# IO.net
KiCad netlist of a schematic drawn in Altium Designer
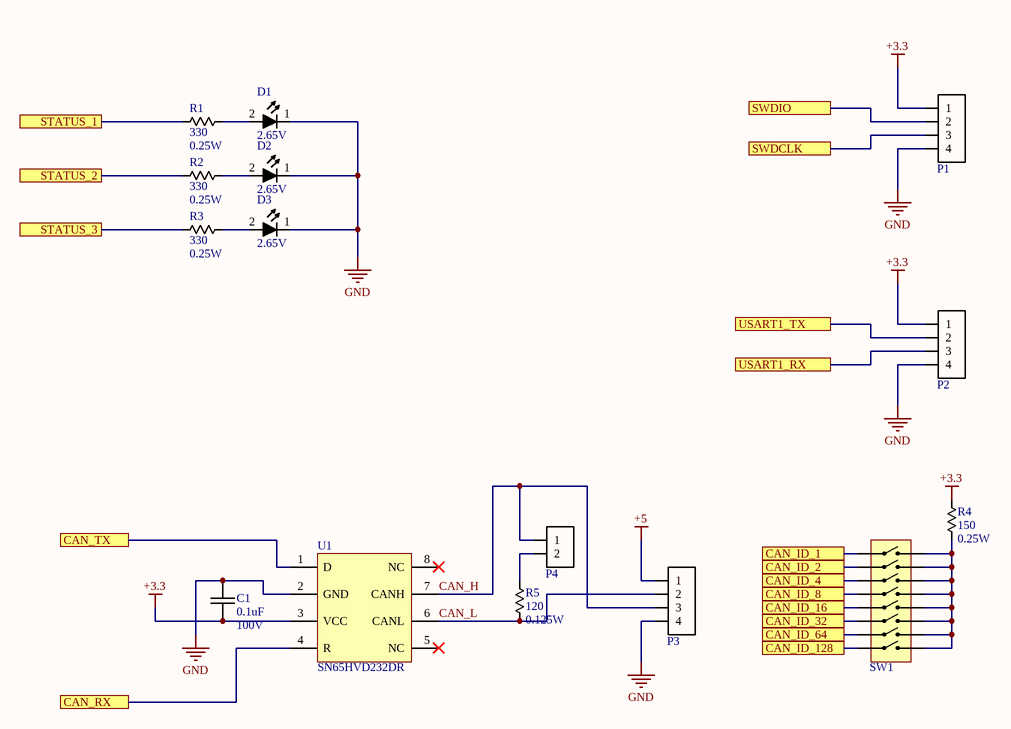
[diagram p0: IO.SchDoc]

(export (version "E")
  (design (tool "Eeschema 10.0.6"))
  (components
    (comp (ref "C1")
      (value "cap_single_np")
      (footprint "chip_0603")
      (description "CAP, 0.1uF, ±10%, 100V, X7R, 0603")
      (fields
        (field (name "TOLERANCE") "±10%")
        (field (name "CAPACITANCE") "0.1uF")
        (field (name "VOLTAGE RATING") "100V")
        (field (name "PART NUMBER") "CAP-00477")
      )
      (libsource (lib "Capacitors") (part "cap_single_np"))
    )
    (comp (ref "D1")
      (value "diode_4")
      (footprint "chip_0603")
      (description "LED, Blue, 0603, Low current, HELI2 Series")
      (fields
        (field (name "FORWARD VOLTAGE") "2.65V")
        (field (name "PART NUMBER") "DIO-00049")
        (field (name "MANUFACTURER") "Kingbright")
      )
      (libsource (lib "Diodes") (part "diode_4"))
    )
    (comp (ref "D2")
      (value "diode_4")
      (footprint "chip_0603")
      (description "LED, Blue, 0603, Low current, HELI2 Series")
      (fields
        (field (name "FORWARD VOLTAGE") "2.65V")
        (field (name "PART NUMBER") "DIO-00049")
        (field (name "MANUFACTURER") "Kingbright")
      )
      (libsource (lib "Diodes") (part "diode_4"))
    )
    (comp (ref "D3")
      (value "diode_4")
      (footprint "chip_0603")
      (description "LED, Blue, 0603, Low current, HELI2 Series")
      (fields
        (field (name "FORWARD VOLTAGE") "2.65V")
        (field (name "PART NUMBER") "DIO-00049")
        (field (name "MANUFACTURER") "Kingbright")
      )
      (libsource (lib "Diodes") (part "diode_4"))
    )
    (comp (ref "P1")
      (value "conn-4x1_0")
      (footprint "HDDR_4x1_0")
      (description "Header 4x1, 0.1\"")
      (fields (field (name "PART NUMBER") "CONN-00029"))
      (libsource (lib "Connectors") (part "conn-4x1_0"))
    )
    (comp (ref "P2")
      (value "conn-4x1_0")
      (footprint "HDDR_4x1_0")
      (description "Header 4x1, 0.1\"")
      (fields (field (name "PART NUMBER") "CONN-00029"))
      (libsource (lib "Connectors") (part "conn-4x1_0"))
    )
    (comp (ref "P3")
      (value "conn-4x1_0")
      (footprint "TERM_3.50MM_4x1_0")
      (description "Term Blk, 4 Pos, 16A, 3.5mm Pitch")
      (fields (field (name "PART NUMBER") "CONN-00024") (field (name "MANUFACTURER") "Phoenix Contact"))
      (libsource (lib "Connectors") (part "conn-4x1_0"))
    )
    (comp (ref "P4")
      (value "conn-2x1_0")
      (footprint "hddr_2x1_0")
      (description "Header, 2x1, 0.1\"")
      (fields (field (name "PART NUMBER") "CONN-00055") (field (name "MANUFACTURER") "Samtec"))
      (libsource (lib "Connectors") (part "conn-2x1_0"))
    )
    (comp (ref "R1")
      (value "res_single")
      (footprint "chip_0603")
      (description "RES SMD 330 OHM 1% 1/4W 0603")
      (fields
        (field (name "TOLERANCE") "1%")
        (field (name "RESISTANCE") "330")
        (field (name "POWER RATING") "0.25W")
        (field (name "PART NUMBER") "RES-00221")
      )
      (libsource (lib "Resistors") (part "res_single"))
    )
    (comp (ref "R2")
      (value "res_single")
      (footprint "chip_0603")
      (description "RES SMD 330 OHM 1% 1/4W 0603")
      (fields
        (field (name "TOLERANCE") "1%")
        (field (name "RESISTANCE") "330")
        (field (name "POWER RATING") "0.25W")
        (field (name "PART NUMBER") "RES-00221")
      )
      (libsource (lib "Resistors") (part "res_single"))
    )
    (comp (ref "R3")
      (value "res_single")
      (footprint "chip_0603")
      (description "RES SMD 330 OHM 1% 1/4W 0603")
      (fields
        (field (name "TOLERANCE") "1%")
        (field (name "RESISTANCE") "330")
        (field (name "POWER RATING") "0.25W")
        (field (name "PART NUMBER") "RES-00221")
      )
      (libsource (lib "Resistors") (part "res_single"))
    )
    (comp (ref "R4")
      (value "res_single")
      (footprint "chip_0603")
      (description "RES SMD 150 OHM 1% 1/4W 0603")
      (fields
        (field (name "TOLERANCE") "1%")
        (field (name "RESISTANCE") "150")
        (field (name "POWER RATING") "0.25W")
        (field (name "PART NUMBER") "RES-00188")
      )
      (libsource (lib "Resistors") (part "res_single"))
    )
    (comp (ref "R5")
      (value "res_single")
      (footprint "chip_0805")
      (description "RES SMD 120 OHM 1% 1/8W 0805")
      (fields
        (field (name "TOLERANCE") "1%")
        (field (name "RESISTANCE") "120")
        (field (name "POWER RATING") "0.125W")
        (field (name "PART NUMBER") "RES-00183")
      )
      (libsource (lib "Resistors") (part "res_single"))
    )
    (comp (ref "SW1")
      (value "DIP_SW_8")
      (footprint "A6S-8104-H")
      (description "DIP Switch, 8 Switches, SMD, 25mA, 24V")
      (fields (field (name "PART NUMBER") "MISC-00045") (field (name "MANUFACTURER") "Omron"))
      (libsource (lib "Misc") (part "DIP_SW_8"))
    )
    (comp (ref "U1")
      (value "SN65HVD232")
      (footprint "SO-8")
      (description "CANbus Transceiver, Single channel, SN65HVD232")
      (fields
        (field (name "MANUFACTURER PN") "SN65HVD232DR")
        (field (name "PART NUMBER") "IFACE-00008")
        (field (name "MANUFACTURER") "TI")
      )
      (libsource (lib "Interfaces") (part "SN65HVD232"))
    )
  )
  (nets
    (net (code "1") (name "+3.3") (class "Default")
      (node (ref "C1") (pin "2") (pinfunction "2_2") (pintype "passive"))
      (node (ref "P1") (pin "1") (pinfunction "1_1") (pintype "passive"))
      (node (ref "P2") (pin "1") (pinfunction "1_1") (pintype "passive"))
      (node (ref "R4") (pin "2") (pinfunction "2_2") (pintype "passive"))
      (node (ref "U1") (pin "3") (pinfunction "VCC_3") (pintype "passive"))
    )
    (net (code "2") (name "+5") (class "Default")
      (node (ref "P3") (pin "1") (pinfunction "1_1") (pintype "passive"))
    )
    (net (code "3") (name "/CAN_H") (class "Default")
      (node (ref "P3") (pin "3") (pinfunction "3_3") (pintype "passive"))
      (node (ref "P4") (pin "1") (pinfunction "1_1") (pintype "passive"))
      (node (ref "U1") (pin "7") (pinfunction "CANH_7") (pintype "passive"))
    )
    (net (code "4") (name "/CAN_ID_1") (class "Default")
      (node (ref "SW1") (pin "1") (pinfunction "1_1") (pintype "passive"))
    )
    (net (code "5") (name "/CAN_ID_2") (class "Default")
      (node (ref "SW1") (pin "2") (pinfunction "2_2") (pintype "passive"))
    )
    (net (code "6") (name "/CAN_ID_4") (class "Default")
      (node (ref "SW1") (pin "3") (pinfunction "3_3") (pintype "passive"))
    )
    (net (code "7") (name "/CAN_ID_8") (class "Default")
      (node (ref "SW1") (pin "4") (pinfunction "4_4") (pintype "passive"))
    )
    (net (code "8") (name "/CAN_ID_16") (class "Default")
      (node (ref "SW1") (pin "5") (pinfunction "5_5") (pintype "passive"))
    )
    (net (code "9") (name "/CAN_ID_32") (class "Default")
      (node (ref "SW1") (pin "6") (pinfunction "6_6") (pintype "passive"))
    )
    (net (code "10") (name "/CAN_ID_64") (class "Default")
      (node (ref "SW1") (pin "7") (pinfunction "7_7") (pintype "passive"))
    )
    (net (code "11") (name "/CAN_ID_128") (class "Default")
      (node (ref "SW1") (pin "8") (pinfunction "8_8") (pintype "passive"))
    )
    (net (code "12") (name "/CAN_L") (class "Default")
      (node (ref "P3") (pin "2") (pinfunction "2_2") (pintype "passive"))
      (node (ref "R5") (pin "2") (pinfunction "2_2") (pintype "passive"))
      (node (ref "U1") (pin "6") (pinfunction "CANL_6") (pintype "passive"))
    )
    (net (code "13") (name "/CAN_RX") (class "Default")
      (node (ref "U1") (pin "4") (pinfunction "R_4") (pintype "passive"))
    )
    (net (code "14") (name "/CAN_TX") (class "Default")
      (node (ref "U1") (pin "1") (pinfunction "D_1") (pintype "passive"))
    )
    (net (code "15") (name "/STATUS_1") (class "Default")
      (node (ref "R1") (pin "1") (pinfunction "1_1") (pintype "passive"))
    )
    (net (code "16") (name "/STATUS_2") (class "Default")
      (node (ref "R2") (pin "1") (pinfunction "1_1") (pintype "passive"))
    )
    (net (code "17") (name "/STATUS_3") (class "Default")
      (node (ref "R3") (pin "1") (pinfunction "1_1") (pintype "passive"))
    )
    (net (code "18") (name "/SWDCLK") (class "Default")
      (node (ref "P1") (pin "3") (pinfunction "3_3") (pintype "passive"))
    )
    (net (code "19") (name "/SWDIO") (class "Default")
      (node (ref "P1") (pin "2") (pinfunction "2_2") (pintype "passive"))
    )
    (net (code "20") (name "/USART1_RX") (class "Default")
      (node (ref "P2") (pin "3") (pinfunction "3_3") (pintype "passive"))
    )
    (net (code "21") (name "/USART1_TX") (class "Default")
      (node (ref "P2") (pin "2") (pinfunction "2_2") (pintype "passive"))
    )
    (net (code "22") (name "GND") (class "Default")
      (node (ref "C1") (pin "1") (pinfunction "1_1") (pintype "passive"))
      (node (ref "D1") (pin "1") (pinfunction "1_1") (pintype "passive"))
      (node (ref "D2") (pin "1") (pinfunction "1_1") (pintype "passive"))
      (node (ref "D3") (pin "1") (pinfunction "1_1") (pintype "passive"))
      (node (ref "P1") (pin "4") (pinfunction "4_4") (pintype "passive"))
      (node (ref "P2") (pin "4") (pinfunction "4_4") (pintype "passive"))
      (node (ref "P3") (pin "4") (pinfunction "4_4") (pintype "passive"))
      (node (ref "U1") (pin "2") (pinfunction "GND_2") (pintype "passive"))
    )
    (net (code "23") (name "Net-(D1-Pad2)") (class "Default")
      (node (ref "D1") (pin "2") (pinfunction "2_2") (pintype "passive"))
      (node (ref "R1") (pin "2") (pinfunction "2_2") (pintype "passive"))
    )
    (net (code "24") (name "Net-(D2-Pad2)") (class "Default")
      (node (ref "D2") (pin "2") (pinfunction "2_2") (pintype "passive"))
      (node (ref "R2") (pin "2") (pinfunction "2_2") (pintype "passive"))
    )
    (net (code "25") (name "Net-(D3-Pad2)") (class "Default")
      (node (ref "D3") (pin "2") (pinfunction "2_2") (pintype "passive"))
      (node (ref "R3") (pin "2") (pinfunction "2_2") (pintype "passive"))
    )
    (net (code "26") (name "Net-(P4-Pad2)") (class "Default")
      (node (ref "P4") (pin "2") (pinfunction "2_2") (pintype "passive"))
      (node (ref "R5") (pin "1") (pinfunction "1_1") (pintype "passive"))
    )
    (net (code "27") (name "Net-(R4-Pad1)") (class "Default")
      (node (ref "R4") (pin "1") (pinfunction "1_1") (pintype "passive"))
      (node (ref "SW1") (pin "10") (pinfunction "10_10") (pintype "passive"))
      (node (ref "SW1") (pin "11") (pinfunction "11_11") (pintype "passive"))
      (node (ref "SW1") (pin "12") (pinfunction "12_12") (pintype "passive"))
      (node (ref "SW1") (pin "13") (pinfunction "13_13") (pintype "passive"))
      (node (ref "SW1") (pin "14") (pinfunction "14_14") (pintype "passive"))
      (node (ref "SW1") (pin "15") (pinfunction "15_15") (pintype "passive"))
      (node (ref "SW1") (pin "16") (pinfunction "16_16") (pintype "passive"))
      (node (ref "SW1") (pin "9") (pinfunction "9_9") (pintype "passive"))
    )
    (net (code "28") (name "unconnected-(U1-NC-Pad5)") (class "Default")
      (node (ref "U1") (pin "5") (pinfunction "NC_5") (pintype "passive+no_connect"))
    )
    (net (code "29") (name "unconnected-(U1-NC-Pad8)") (class "Default")
      (node (ref "U1") (pin "8") (pinfunction "NC_8") (pintype "passive+no_connect"))
    )
  )
)
